# Remote.net
KiCad netlist of a schematic drawn in EAGLE
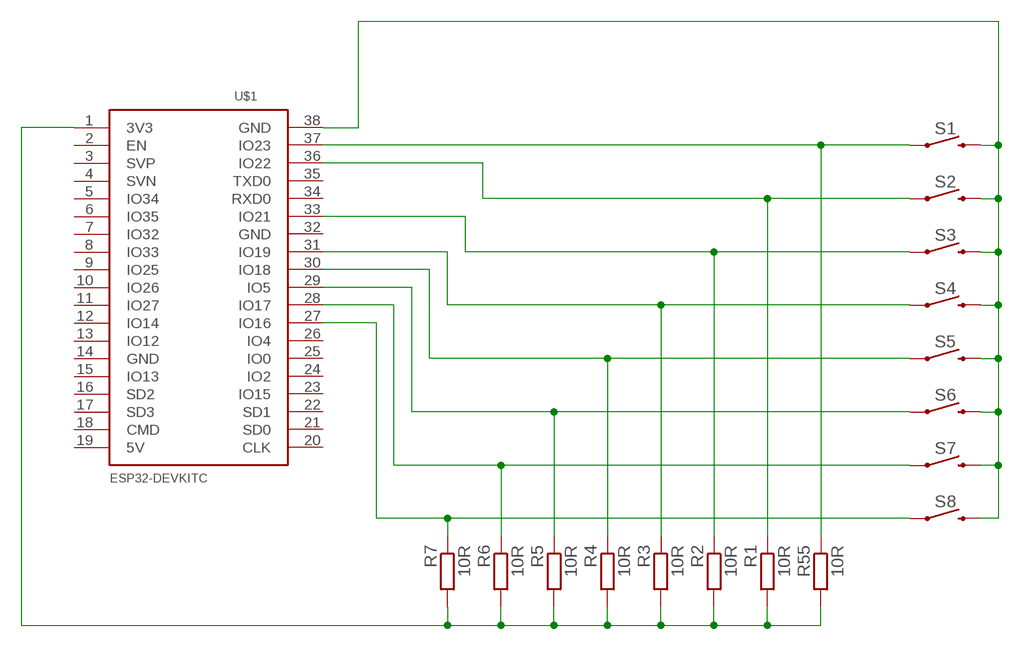
[diagram p0: schematic, sheet 1]

(export (version "E")
  (design (tool "Eeschema 10.0.6"))
  (components
    (comp (ref "R1")
      (value "10R")
      (footprint "eagle-import:0204_7")
      (libsource (lib "eagle-import") (part "R-EU_0204/7"))
    )
    (comp (ref "R2")
      (value "10R")
      (footprint "eagle-import:0204_7")
      (libsource (lib "eagle-import") (part "R-EU_0204/7"))
    )
    (comp (ref "R3")
      (value "10R")
      (footprint "eagle-import:0204_7")
      (libsource (lib "eagle-import") (part "R-EU_0204/7"))
    )
    (comp (ref "R4")
      (value "10R")
      (footprint "eagle-import:0204_7")
      (libsource (lib "eagle-import") (part "R-EU_0204/7"))
    )
    (comp (ref "R5")
      (value "10R")
      (footprint "eagle-import:0204_7")
      (libsource (lib "eagle-import") (part "R-EU_0204/7"))
    )
    (comp (ref "R6")
      (value "10R")
      (footprint "eagle-import:0204_7")
      (libsource (lib "eagle-import") (part "R-EU_0204/7"))
    )
    (comp (ref "R7")
      (value "10R")
      (footprint "eagle-import:0204_7")
      (libsource (lib "eagle-import") (part "R-EU_0204/7"))
    )
    (comp (ref "R55")
      (value "10R")
      (footprint "eagle-import:0204_7")
      (libsource (lib "eagle-import") (part "R-EU_0204/7"))
    )
    (comp (ref "S1")
      (value "MOMENTARY-SWITCH-SPST-PTH-12MM")
      (footprint "eagle-import:TACTILE_SWITCH_PTH_12MM")
      (libsource (lib "eagle-import") (part "MOMENTARY-SWITCH-SPST-PTH-12MM"))
    )
    (comp (ref "S2")
      (value "MOMENTARY-SWITCH-SPST-PTH-12MM")
      (footprint "eagle-import:TACTILE_SWITCH_PTH_12MM")
      (libsource (lib "eagle-import") (part "MOMENTARY-SWITCH-SPST-PTH-12MM"))
    )
    (comp (ref "S3")
      (value "MOMENTARY-SWITCH-SPST-PTH-12MM")
      (footprint "eagle-import:TACTILE_SWITCH_PTH_12MM")
      (libsource (lib "eagle-import") (part "MOMENTARY-SWITCH-SPST-PTH-12MM"))
    )
    (comp (ref "S4")
      (value "MOMENTARY-SWITCH-SPST-PTH-12MM")
      (footprint "eagle-import:TACTILE_SWITCH_PTH_12MM")
      (libsource (lib "eagle-import") (part "MOMENTARY-SWITCH-SPST-PTH-12MM"))
    )
    (comp (ref "S5")
      (value "MOMENTARY-SWITCH-SPST-PTH-12MM")
      (footprint "eagle-import:TACTILE_SWITCH_PTH_12MM")
      (libsource (lib "eagle-import") (part "MOMENTARY-SWITCH-SPST-PTH-12MM"))
    )
    (comp (ref "S6")
      (value "MOMENTARY-SWITCH-SPST-PTH-12MM")
      (footprint "eagle-import:TACTILE_SWITCH_PTH_12MM")
      (libsource (lib "eagle-import") (part "MOMENTARY-SWITCH-SPST-PTH-12MM"))
    )
    (comp (ref "S7")
      (value "MOMENTARY-SWITCH-SPST-PTH-12MM")
      (footprint "eagle-import:TACTILE_SWITCH_PTH_12MM")
      (libsource (lib "eagle-import") (part "MOMENTARY-SWITCH-SPST-PTH-12MM"))
    )
    (comp (ref "S8")
      (value "MOMENTARY-SWITCH-SPST-PTH-12MM")
      (footprint "eagle-import:TACTILE_SWITCH_PTH_12MM")
      (libsource (lib "eagle-import") (part "MOMENTARY-SWITCH-SPST-PTH-12MM"))
    )
    (comp (ref "U$1")
      (value "ESP32NODEMCU")
      (footprint "eagle-import:ESP32NODEMCU")
      (libsource (lib "eagle-import") (part "ESP32NODEMCU"))
    )
  )
  (nets
    (net (code "1") (name "Net-(S1-2)") (class "Default")
      (node (ref "S1") (pin "3") (pinfunction "2_3") (pintype "passive"))
      (node (ref "S2") (pin "3") (pinfunction "2_3") (pintype "passive"))
      (node (ref "S3") (pin "3") (pinfunction "2_3") (pintype "passive"))
      (node (ref "S4") (pin "3") (pinfunction "2_3") (pintype "passive"))
      (node (ref "S5") (pin "3") (pinfunction "2_3") (pintype "passive"))
      (node (ref "S6") (pin "3") (pinfunction "2_3") (pintype "passive"))
      (node (ref "S7") (pin "3") (pinfunction "2_3") (pintype "passive"))
      (node (ref "S8") (pin "3") (pinfunction "2_3") (pintype "passive"))
      (node (ref "U$1") (pin "38") (pinfunction "GND_38") (pintype "bidirectional"))
    )
    (net (code "2") (name "Net-(U$1-3V3)") (class "Default")
      (node (ref "R1") (pin "2") (pinfunction "2_2") (pintype "passive"))
      (node (ref "R2") (pin "2") (pinfunction "2_2") (pintype "passive"))
      (node (ref "R3") (pin "2") (pinfunction "2_2") (pintype "passive"))
      (node (ref "R4") (pin "2") (pinfunction "2_2") (pintype "passive"))
      (node (ref "R5") (pin "2") (pinfunction "2_2") (pintype "passive"))
      (node (ref "R55") (pin "2") (pinfunction "2_2") (pintype "passive"))
      (node (ref "R6") (pin "2") (pinfunction "2_2") (pintype "passive"))
      (node (ref "R7") (pin "2") (pinfunction "2_2") (pintype "passive"))
      (node (ref "U$1") (pin "1") (pinfunction "3V3_1") (pintype "bidirectional"))
    )
    (net (code "3") (name "Net-(U$1-IO5)") (class "Default")
      (node (ref "R5") (pin "1") (pinfunction "1_1") (pintype "passive"))
      (node (ref "S6") (pin "1") (pinfunction "1_1") (pintype "passive"))
      (node (ref "U$1") (pin "29") (pinfunction "IO5_29") (pintype "bidirectional"))
    )
    (net (code "4") (name "Net-(U$1-IO16)") (class "Default")
      (node (ref "R7") (pin "1") (pinfunction "1_1") (pintype "passive"))
      (node (ref "S8") (pin "1") (pinfunction "1_1") (pintype "passive"))
      (node (ref "U$1") (pin "27") (pinfunction "IO16_27") (pintype "bidirectional"))
    )
    (net (code "5") (name "Net-(U$1-IO17)") (class "Default")
      (node (ref "R6") (pin "1") (pinfunction "1_1") (pintype "passive"))
      (node (ref "S7") (pin "1") (pinfunction "1_1") (pintype "passive"))
      (node (ref "U$1") (pin "28") (pinfunction "IO17_28") (pintype "bidirectional"))
    )
    (net (code "6") (name "Net-(U$1-IO18)") (class "Default")
      (node (ref "R4") (pin "1") (pinfunction "1_1") (pintype "passive"))
      (node (ref "S5") (pin "1") (pinfunction "1_1") (pintype "passive"))
      (node (ref "U$1") (pin "30") (pinfunction "IO18_30") (pintype "bidirectional"))
    )
    (net (code "7") (name "Net-(U$1-IO19)") (class "Default")
      (node (ref "R3") (pin "1") (pinfunction "1_1") (pintype "passive"))
      (node (ref "S4") (pin "1") (pinfunction "1_1") (pintype "passive"))
      (node (ref "U$1") (pin "31") (pinfunction "IO19_31") (pintype "bidirectional"))
    )
    (net (code "8") (name "Net-(U$1-IO21)") (class "Default")
      (node (ref "R2") (pin "1") (pinfunction "1_1") (pintype "passive"))
      (node (ref "S3") (pin "1") (pinfunction "1_1") (pintype "passive"))
      (node (ref "U$1") (pin "33") (pinfunction "IO21_33") (pintype "bidirectional"))
    )
    (net (code "9") (name "Net-(U$1-IO22)") (class "Default")
      (node (ref "R1") (pin "1") (pinfunction "1_1") (pintype "passive"))
      (node (ref "S2") (pin "1") (pinfunction "1_1") (pintype "passive"))
      (node (ref "U$1") (pin "36") (pinfunction "IO22_36") (pintype "bidirectional"))
    )
    (net (code "10") (name "Net-(U$1-IO23)") (class "Default")
      (node (ref "R55") (pin "1") (pinfunction "1_1") (pintype "passive"))
      (node (ref "S1") (pin "1") (pinfunction "1_1") (pintype "passive"))
      (node (ref "U$1") (pin "37") (pinfunction "IO23_37") (pintype "bidirectional"))
    )
    (net (code "11") (name "unconnected-(U$1-5V-Pad19)") (class "Default")
      (node (ref "U$1") (pin "19") (pinfunction "5V_19") (pintype "bidirectional"))
    )
    (net (code "12") (name "unconnected-(U$1-CLK-Pad20)") (class "Default")
      (node (ref "U$1") (pin "20") (pinfunction "CLK_20") (pintype "bidirectional"))
    )
    (net (code "13") (name "unconnected-(U$1-CMD-Pad18)") (class "Default")
      (node (ref "U$1") (pin "18") (pinfunction "CMD_18") (pintype "bidirectional"))
    )
    (net (code "14") (name "unconnected-(U$1-EN-Pad2)") (class "Default")
      (node (ref "U$1") (pin "2") (pinfunction "EN_2") (pintype "bidirectional"))
    )
    (net (code "15") (name "unconnected-(U$1-GND-Pad14)") (class "Default")
      (node (ref "U$1") (pin "14") (pinfunction "GND_14") (pintype "bidirectional"))
    )
    (net (code "16") (name "unconnected-(U$1-GND-Pad32)") (class "Default")
      (node (ref "U$1") (pin "32") (pinfunction "GND_32") (pintype "bidirectional"))
    )
    (net (code "17") (name "unconnected-(U$1-IO0-Pad25)") (class "Default")
      (node (ref "U$1") (pin "25") (pinfunction "IO0_25") (pintype "bidirectional"))
    )
    (net (code "18") (name "unconnected-(U$1-IO2-Pad24)") (class "Default")
      (node (ref "U$1") (pin "24") (pinfunction "IO2_24") (pintype "bidirectional"))
    )
    (net (code "19") (name "unconnected-(U$1-IO4-Pad26)") (class "Default")
      (node (ref "U$1") (pin "26") (pinfunction "IO4_26") (pintype "bidirectional"))
    )
    (net (code "20") (name "unconnected-(U$1-IO12-Pad13)") (class "Default")
      (node (ref "U$1") (pin "13") (pinfunction "IO12_13") (pintype "bidirectional"))
    )
    (net (code "21") (name "unconnected-(U$1-IO13-Pad15)") (class "Default")
      (node (ref "U$1") (pin "15") (pinfunction "IO13_15") (pintype "bidirectional"))
    )
    (net (code "22") (name "unconnected-(U$1-IO14-Pad12)") (class "Default")
      (node (ref "U$1") (pin "12") (pinfunction "IO14_12") (pintype "bidirectional"))
    )
    (net (code "23") (name "unconnected-(U$1-IO15-Pad23)") (class "Default")
      (node (ref "U$1") (pin "23") (pinfunction "IO15_23") (pintype "bidirectional"))
    )
    (net (code "24") (name "unconnected-(U$1-IO25-Pad9)") (class "Default")
      (node (ref "U$1") (pin "9") (pinfunction "IO25_9") (pintype "bidirectional"))
    )
    (net (code "25") (name "unconnected-(U$1-IO26-Pad10)") (class "Default")
      (node (ref "U$1") (pin "10") (pinfunction "IO26_10") (pintype "bidirectional"))
    )
    (net (code "26") (name "unconnected-(U$1-IO27-Pad11)") (class "Default")
      (node (ref "U$1") (pin "11") (pinfunction "IO27_11") (pintype "bidirectional"))
    )
    (net (code "27") (name "unconnected-(U$1-IO32-Pad7)") (class "Default")
      (node (ref "U$1") (pin "7") (pinfunction "IO32_7") (pintype "bidirectional"))
    )
    (net (code "28") (name "unconnected-(U$1-IO33-Pad8)") (class "Default")
      (node (ref "U$1") (pin "8") (pinfunction "IO33_8") (pintype "bidirectional"))
    )
    (net (code "29") (name "unconnected-(U$1-IO34-Pad5)") (class "Default")
      (node (ref "U$1") (pin "5") (pinfunction "IO34_5") (pintype "bidirectional"))
    )
    (net (code "30") (name "unconnected-(U$1-IO35-Pad6)") (class "Default")
      (node (ref "U$1") (pin "6") (pinfunction "IO35_6") (pintype "bidirectional"))
    )
    (net (code "31") (name "unconnected-(U$1-RXD0-Pad34)") (class "Default")
      (node (ref "U$1") (pin "34") (pinfunction "RXD0_34") (pintype "bidirectional"))
    )
    (net (code "32") (name "unconnected-(U$1-SD0-Pad21)") (class "Default")
      (node (ref "U$1") (pin "21") (pinfunction "SD0_21") (pintype "bidirectional"))
    )
    (net (code "33") (name "unconnected-(U$1-SD1-Pad22)") (class "Default")
      (node (ref "U$1") (pin "22") (pinfunction "SD1_22") (pintype "bidirectional"))
    )
    (net (code "34") (name "unconnected-(U$1-SD2-Pad16)") (class "Default")
      (node (ref "U$1") (pin "16") (pinfunction "SD2_16") (pintype "bidirectional"))
    )
    (net (code "35") (name "unconnected-(U$1-SD3-Pad17)") (class "Default")
      (node (ref "U$1") (pin "17") (pinfunction "SD3_17") (pintype "bidirectional"))
    )
    (net (code "36") (name "unconnected-(U$1-SVN-Pad4)") (class "Default")
      (node (ref "U$1") (pin "4") (pinfunction "SVN_4") (pintype "bidirectional"))
    )
    (net (code "37") (name "unconnected-(U$1-SVP-Pad3)") (class "Default")
      (node (ref "U$1") (pin "3") (pinfunction "SVP_3") (pintype "bidirectional"))
    )
    (net (code "38") (name "unconnected-(U$1-TXD0-Pad35)") (class "Default")
      (node (ref "U$1") (pin "35") (pinfunction "TXD0_35") (pintype "bidirectional"))
    )
  )
)
